# OpAmp-Inverting-3Transistor-alt3.net
KiCad netlist of a schematic drawn in EAGLE
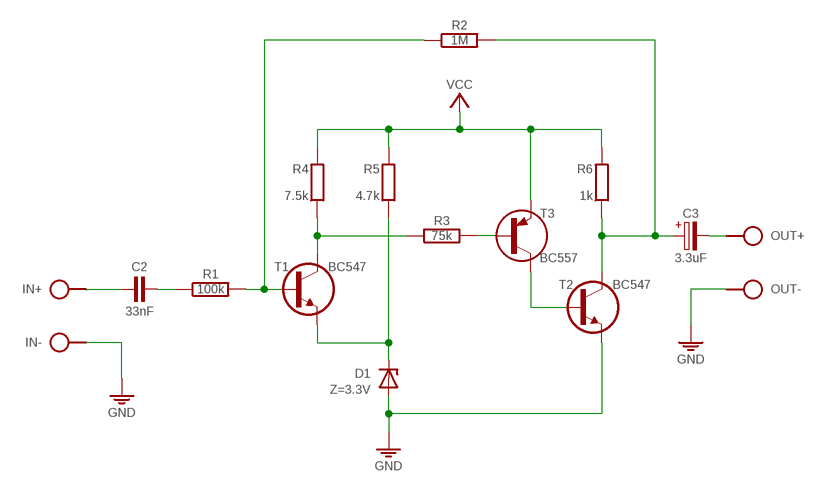
[diagram p0: schematic, sheet 1]

(export (version "E")
  (design (tool "Eeschema 10.0.6"))
  (components
    (comp (ref "C2")
      (value "33nF")
      (footprint "eagle-import:C050-020X044")
      (libsource (lib "eagle-import") (part "C050-020X044"))
    )
    (comp (ref "C3")
      (value "3.3uF")
      (footprint "eagle-import:E2.5-4_V")
      (libsource (lib "eagle-import") (part "CPOLE2,5-4/V"))
    )
    (comp (ref "D1")
      (value "Z=3.3V")
      (footprint "eagle-import:DO34Z2,5")
      (libsource (lib "eagle-import") (part "Z-DIODE34Z2,5"))
    )
    (comp (ref "IN")
      (value "SPAD+--+")
      (footprint "eagle-import:SPAD-+")
      (libsource (lib "eagle-import") (part "SPAD+--+"))
    )
    (comp (ref "J1")
      (value "VCC_GNDPWR-R")
      (footprint "eagle-import:PWR-R")
      (libsource (lib "eagle-import") (part "VCC_GNDPWR-R"))
    )
    (comp (ref "OUT")
      (value "SPAD+-+-")
      (footprint "eagle-import:SPAD+-")
      (libsource (lib "eagle-import") (part "SPAD+-+-"))
    )
    (comp (ref "R1")
      (value "100k")
      (footprint "eagle-import:0202_10-V")
      (libsource (lib "eagle-import") (part "R-H0202/10-V"))
    )
    (comp (ref "R2")
      (value "1M")
      (footprint "eagle-import:0202_10")
      (libsource (lib "eagle-import") (part "R-H0202/10"))
    )
    (comp (ref "R3")
      (value "75k")
      (footprint "eagle-import:0202_7")
      (libsource (lib "eagle-import") (part "R-H0202/7"))
    )
    (comp (ref "R4")
      (value "7.5k")
      (footprint "eagle-import:0202_7")
      (libsource (lib "eagle-import") (part "R0202/7"))
    )
    (comp (ref "R5")
      (value "4.7k")
      (footprint "eagle-import:0202_7")
      (libsource (lib "eagle-import") (part "R0202/7"))
    )
    (comp (ref "R6")
      (value "1k")
      (footprint "eagle-import:0202_10-V")
      (libsource (lib "eagle-import") (part "R0202/10-V"))
    )
    (comp (ref "T1")
      (value "BC547")
      (footprint "eagle-import:TO92-CBE")
      (libsource (lib "eagle-import") (part "BC547CBE"))
    )
    (comp (ref "T2")
      (value "BC547")
      (footprint "eagle-import:TO92-CBE")
      (libsource (lib "eagle-import") (part "BC547CBE"))
    )
    (comp (ref "T3")
      (value "BC557")
      (footprint "eagle-import:TO92-CBE")
      (libsource (lib "eagle-import") (part "BC557CBE"))
    )
  )
  (nets
    (net (code "1") (name "GND") (class "Default")
      (node (ref "D1") (pin "A") (pinfunction "A_A") (pintype "passive"))
      (node (ref "IN") (pin "1") (pinfunction "P$1_1") (pintype "passive"))
      (node (ref "J1") (pin "1") (pinfunction "GND_1") (pintype "power_in"))
      (node (ref "OUT") (pin "1") (pinfunction "P$1_1") (pintype "passive"))
      (node (ref "T2") (pin "E") (pinfunction "E_E") (pintype "passive"))
    )
    (net (code "2") (name "Net-(C2-Pad1)") (class "Default")
      (node (ref "C2") (pin "1") (pinfunction "1_1") (pintype "passive"))
      (node (ref "R1") (pin "1") (pinfunction "1_1") (pintype "passive"))
    )
    (net (code "3") (name "Net-(C3-Pad+)") (class "Default")
      (node (ref "C3") (pin "+") (pinfunction "+_+") (pintype "passive"))
      (node (ref "R2") (pin "2") (pinfunction "2_2") (pintype "passive"))
      (node (ref "R6") (pin "2") (pinfunction "2_2") (pintype "passive"))
      (node (ref "T2") (pin "C") (pinfunction "C_C") (pintype "passive"))
    )
    (net (code "4") (name "Net-(D1-PadC)") (class "Default")
      (node (ref "D1") (pin "C") (pinfunction "C_C") (pintype "passive"))
      (node (ref "R5") (pin "2") (pinfunction "2_2") (pintype "passive"))
      (node (ref "T1") (pin "E") (pinfunction "E_E") (pintype "passive"))
    )
    (net (code "5") (name "Net-(INA-P$1)") (class "Default")
      (node (ref "C2") (pin "2") (pinfunction "2_2") (pintype "passive"))
      (node (ref "IN") (pin "2") (pinfunction "P$1_2") (pintype "passive"))
    )
    (net (code "6") (name "Net-(J1A-VCC)") (class "Default")
      (node (ref "J1") (pin "2") (pinfunction "VCC_2") (pintype "power_in"))
      (node (ref "R4") (pin "1") (pinfunction "1_1") (pintype "passive"))
      (node (ref "R5") (pin "1") (pinfunction "1_1") (pintype "passive"))
      (node (ref "R6") (pin "1") (pinfunction "1_1") (pintype "passive"))
      (node (ref "T3") (pin "E") (pinfunction "E_E") (pintype "passive"))
    )
    (net (code "7") (name "Net-(OUTA-P$1)") (class "Default")
      (node (ref "C3") (pin "-") (pinfunction "-_-") (pintype "passive"))
      (node (ref "OUT") (pin "2") (pinfunction "P$1_2") (pintype "passive"))
    )
    (net (code "8") (name "Net-(R1-Pad2)") (class "Default")
      (node (ref "R1") (pin "2") (pinfunction "2_2") (pintype "passive"))
      (node (ref "R2") (pin "1") (pinfunction "1_1") (pintype "passive"))
      (node (ref "T1") (pin "B") (pinfunction "B_B") (pintype "passive"))
    )
    (net (code "9") (name "Net-(R3-Pad1)") (class "Default")
      (node (ref "R3") (pin "1") (pinfunction "1_1") (pintype "passive"))
      (node (ref "R4") (pin "2") (pinfunction "2_2") (pintype "passive"))
      (node (ref "T1") (pin "C") (pinfunction "C_C") (pintype "passive"))
    )
    (net (code "10") (name "Net-(R3-Pad2)") (class "Default")
      (node (ref "R3") (pin "2") (pinfunction "2_2") (pintype "passive"))
      (node (ref "T3") (pin "B") (pinfunction "B_B") (pintype "passive"))
    )
    (net (code "11") (name "Net-(T2-PadB)") (class "Default")
      (node (ref "T2") (pin "B") (pinfunction "B_B") (pintype "passive"))
      (node (ref "T3") (pin "C") (pinfunction "C_C") (pintype "passive"))
    )
  )
)
